# 3dB_Attenuator.net
KiCad netlist of a schematic drawn in Altium Designer
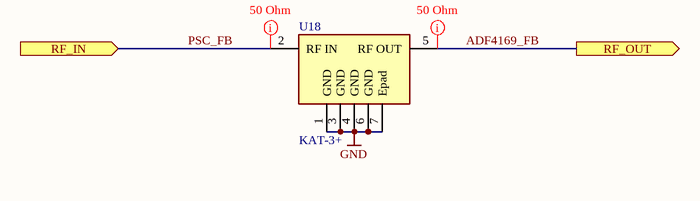
[diagram p0: 3dB_Attenuator.SchDoc]

(export (version "E")
  (design (tool "Eeschema 10.0.6"))
  (components
    (comp (ref "U18")
      (value "KAT-3+")
      (footprint "MC1630-1")
      (fields (field (name "MANUFACTURER") "Minicircuits"))
      (libsource (lib "database_library") (part "KAT-XX+"))
    )
  )
  (nets
    (net (code "1") (name "/ADF4169_FB") (class "Default")
      (node (ref "U18") (pin "5") (pinfunction "RF_OUT_5") (pintype "passive"))
    )
    (net (code "2") (name "/PSC_FB") (class "Default")
      (node (ref "U18") (pin "2") (pinfunction "RF_IN_2") (pintype "passive"))
    )
    (net (code "3") (name "GND") (class "Default")
      (node (ref "U18") (pin "1") (pinfunction "GND_1") (pintype "passive"))
      (node (ref "U18") (pin "3") (pinfunction "GND_3") (pintype "passive"))
      (node (ref "U18") (pin "4") (pinfunction "GND_4") (pintype "passive"))
      (node (ref "U18") (pin "6") (pinfunction "GND_6") (pintype "passive"))
      (node (ref "U18") (pin "7") (pinfunction "Epad_7") (pintype "passive"))
    )
  )
)
